# Circuit_Complet_Sinus.net
KiCad netlist of a schematic drawn in Altium Designer
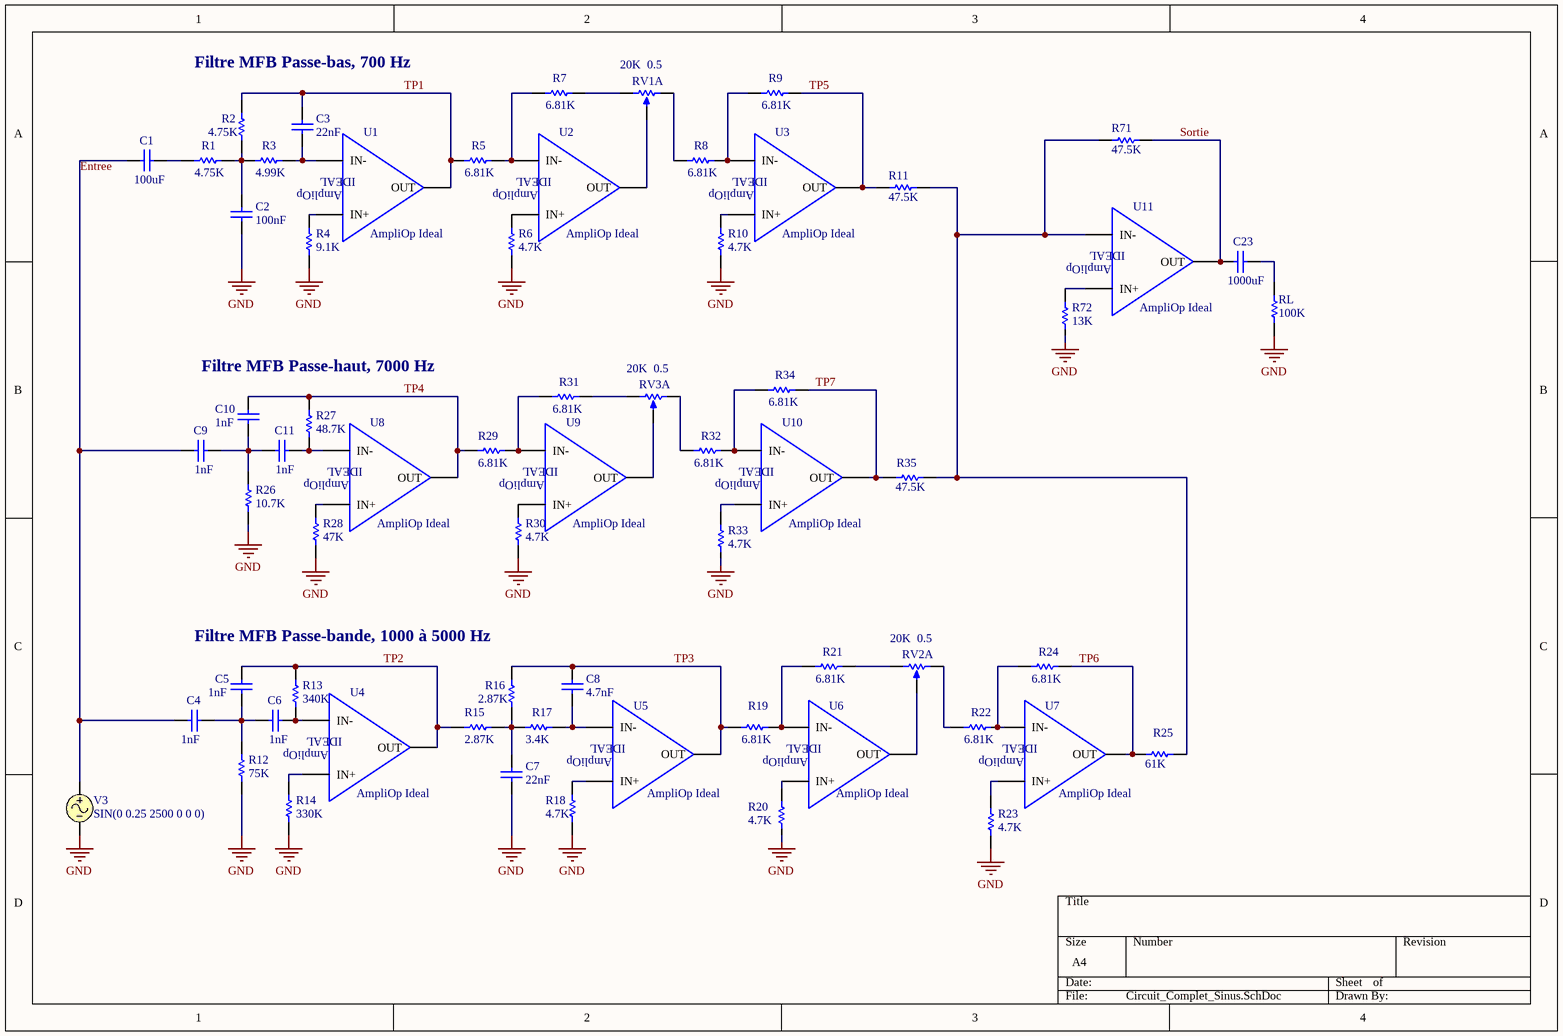
[diagram p0: Circuit_Complet_Sinus.SchDoc]

(export (version "E")
  (design (tool "Eeschema 10.0.6"))
  (components
    (comp (ref "C1")
      (value "100uF")
      (footprint "RAD-0.3")
      (description "Capacitor")
      (fields (field (name "Comment") "Cap") (field (name "PUBLISHER") "Altium Limited"))
      (libsource (lib "Miscellaneous Devices") (part "Cap"))
    )
    (comp (ref "C2")
      (value "100nF")
      (footprint "RAD-0.3")
      (description "Capacitor")
      (fields (field (name "Comment") "Cap") (field (name "PUBLISHER") "Altium Limited"))
      (libsource (lib "Miscellaneous Devices") (part "Cap"))
    )
    (comp (ref "C3")
      (value "22nF")
      (footprint "RAD-0.3")
      (description "Capacitor")
      (fields (field (name "Comment") "Cap") (field (name "PUBLISHER") "Altium Limited"))
      (libsource (lib "Miscellaneous Devices") (part "Cap"))
    )
    (comp (ref "C4")
      (value "1nF")
      (footprint "RAD-0.3")
      (description "Capacitor")
      (fields (field (name "Comment") "Cap") (field (name "PUBLISHER") "Altium Limited"))
      (libsource (lib "Miscellaneous Devices") (part "Cap"))
    )
    (comp (ref "C5")
      (value "1nF")
      (footprint "RAD-0.3")
      (description "Capacitor")
      (fields (field (name "Comment") "Cap") (field (name "PUBLISHER") "Altium Limited"))
      (libsource (lib "Miscellaneous Devices") (part "Cap"))
    )
    (comp (ref "C6")
      (value "1nF")
      (footprint "RAD-0.3")
      (description "Capacitor")
      (fields (field (name "Comment") "Cap") (field (name "PUBLISHER") "Altium Limited"))
      (libsource (lib "Miscellaneous Devices") (part "Cap"))
    )
    (comp (ref "C7")
      (value "22nF")
      (footprint "RAD-0.3")
      (description "Capacitor")
      (fields (field (name "Comment") "Cap") (field (name "PUBLISHER") "Altium Limited"))
      (libsource (lib "Miscellaneous Devices") (part "Cap"))
    )
    (comp (ref "C8")
      (value "4.7nF")
      (footprint "RAD-0.3")
      (description "Capacitor")
      (fields (field (name "Comment") "Cap") (field (name "PUBLISHER") "Altium Limited"))
      (libsource (lib "Miscellaneous Devices") (part "Cap"))
    )
    (comp (ref "C9")
      (value "1nF")
      (footprint "RAD-0.3")
      (description "Capacitor")
      (fields (field (name "Comment") "Cap") (field (name "PUBLISHER") "Altium Limited"))
      (libsource (lib "Miscellaneous Devices") (part "Cap"))
    )
    (comp (ref "C10")
      (value "1nF")
      (footprint "RAD-0.3")
      (description "Capacitor")
      (fields (field (name "Comment") "Cap") (field (name "PUBLISHER") "Altium Limited"))
      (libsource (lib "Miscellaneous Devices") (part "Cap"))
    )
    (comp (ref "C11")
      (value "1nF")
      (footprint "RAD-0.3")
      (description "Capacitor")
      (fields (field (name "Comment") "Cap") (field (name "PUBLISHER") "Altium Limited"))
      (libsource (lib "Miscellaneous Devices") (part "Cap"))
    )
    (comp (ref "C23")
      (value "1000uF")
      (footprint "RAD-0.3")
      (description "Capacitor")
      (fields (field (name "Comment") "Cap") (field (name "PUBLISHER") "Altium Limited"))
      (libsource (lib "Miscellaneous Devices") (part "Cap"))
    )
    (comp (ref "R1")
      (value "4.75K")
      (footprint "AXIAL-0.3")
      (description "Resistor")
      (fields (field (name "Comment") "Res1") (field (name "PUBLISHER") "Altium Limited"))
      (libsource (lib "Miscellaneous Devices") (part "Res1"))
    )
    (comp (ref "R2")
      (value "4.75K")
      (footprint "AXIAL-0.3")
      (description "Resistor")
      (fields (field (name "Comment") "Res1") (field (name "PUBLISHER") "Altium Limited"))
      (libsource (lib "Miscellaneous Devices") (part "Res1"))
    )
    (comp (ref "R3")
      (value "4.99K")
      (footprint "AXIAL-0.3")
      (description "Resistor")
      (fields (field (name "Comment") "Res1") (field (name "PUBLISHER") "Altium Limited"))
      (libsource (lib "Miscellaneous Devices") (part "Res1"))
    )
    (comp (ref "R4")
      (value "9.1K")
      (footprint "AXIAL-0.3")
      (description "Resistor")
      (fields (field (name "Comment") "Res1") (field (name "PUBLISHER") "Altium Limited"))
      (libsource (lib "Miscellaneous Devices") (part "Res1"))
    )
    (comp (ref "R5")
      (value "6.81K")
      (footprint "AXIAL-0.3")
      (description "Resistor")
      (fields (field (name "Comment") "Res1") (field (name "PUBLISHER") "Altium Limited"))
      (libsource (lib "Miscellaneous Devices") (part "Res1"))
    )
    (comp (ref "R6")
      (value "4.7K")
      (footprint "AXIAL-0.3")
      (description "Resistor")
      (fields (field (name "Comment") "Res1") (field (name "PUBLISHER") "Altium Limited"))
      (libsource (lib "Miscellaneous Devices") (part "Res1"))
    )
    (comp (ref "R7")
      (value "6.81K")
      (footprint "AXIAL-0.3")
      (description "Resistor")
      (fields (field (name "Comment") "Res1") (field (name "PUBLISHER") "Altium Limited"))
      (libsource (lib "Miscellaneous Devices") (part "Res1"))
    )
    (comp (ref "R8")
      (value "6.81K")
      (footprint "AXIAL-0.3")
      (description "Resistor")
      (fields (field (name "Comment") "Res1") (field (name "PUBLISHER") "Altium Limited"))
      (libsource (lib "Miscellaneous Devices") (part "Res1"))
    )
    (comp (ref "R9")
      (value "6.81K")
      (footprint "AXIAL-0.3")
      (description "Resistor")
      (fields (field (name "Comment") "Res1") (field (name "PUBLISHER") "Altium Limited"))
      (libsource (lib "Miscellaneous Devices") (part "Res1"))
    )
    (comp (ref "R10")
      (value "4.7K")
      (footprint "AXIAL-0.3")
      (description "Resistor")
      (fields (field (name "Comment") "Res1") (field (name "PUBLISHER") "Altium Limited"))
      (libsource (lib "Miscellaneous Devices") (part "Res1"))
    )
    (comp (ref "R11")
      (value "47.5K")
      (footprint "AXIAL-0.3")
      (description "Resistor")
      (fields (field (name "Comment") "Res1") (field (name "PUBLISHER") "Altium Limited"))
      (libsource (lib "Miscellaneous Devices") (part "Res1"))
    )
    (comp (ref "R12")
      (value "75K")
      (footprint "AXIAL-0.3")
      (description "Resistor")
      (fields (field (name "Comment") "Res1") (field (name "PUBLISHER") "Altium Limited"))
      (libsource (lib "Miscellaneous Devices") (part "Res1"))
    )
    (comp (ref "R13")
      (value "340K")
      (footprint "AXIAL-0.3")
      (description "Resistor")
      (fields (field (name "Comment") "Res1") (field (name "PUBLISHER") "Altium Limited"))
      (libsource (lib "Miscellaneous Devices") (part "Res1"))
    )
    (comp (ref "R14")
      (value "330K")
      (footprint "AXIAL-0.3")
      (description "Resistor")
      (fields (field (name "Comment") "Res1") (field (name "PUBLISHER") "Altium Limited"))
      (libsource (lib "Miscellaneous Devices") (part "Res1"))
    )
    (comp (ref "R15")
      (value "2.87K")
      (footprint "AXIAL-0.3")
      (description "Resistor")
      (fields (field (name "Comment") "Res1") (field (name "PUBLISHER") "Altium Limited"))
      (libsource (lib "Miscellaneous Devices") (part "Res1"))
    )
    (comp (ref "R16")
      (value "2.87K")
      (footprint "AXIAL-0.3")
      (description "Resistor")
      (fields (field (name "Comment") "Res1") (field (name "PUBLISHER") "Altium Limited"))
      (libsource (lib "Miscellaneous Devices") (part "Res1"))
    )
    (comp (ref "R17")
      (value "3.4K")
      (footprint "AXIAL-0.3")
      (description "Resistor")
      (fields (field (name "Comment") "Res1") (field (name "PUBLISHER") "Altium Limited"))
      (libsource (lib "Miscellaneous Devices") (part "Res1"))
    )
    (comp (ref "R18")
      (value "4.7K")
      (footprint "AXIAL-0.3")
      (description "Resistor")
      (fields (field (name "Comment") "Res1") (field (name "PUBLISHER") "Altium Limited"))
      (libsource (lib "Miscellaneous Devices") (part "Res1"))
    )
    (comp (ref "R19")
      (value "6.81K")
      (footprint "AXIAL-0.3")
      (description "Resistor")
      (fields (field (name "Comment") "Res1") (field (name "PUBLISHER") "Altium Limited"))
      (libsource (lib "Miscellaneous Devices") (part "Res1"))
    )
    (comp (ref "R20")
      (value "4.7K")
      (footprint "AXIAL-0.3")
      (description "Resistor")
      (fields (field (name "Comment") "Res1") (field (name "PUBLISHER") "Altium Limited"))
      (libsource (lib "Miscellaneous Devices") (part "Res1"))
    )
    (comp (ref "R21")
      (value "6.81K")
      (footprint "AXIAL-0.3")
      (description "Resistor")
      (fields (field (name "Comment") "Res1") (field (name "PUBLISHER") "Altium Limited"))
      (libsource (lib "Miscellaneous Devices") (part "Res1"))
    )
    (comp (ref "R22")
      (value "6.81K")
      (footprint "AXIAL-0.3")
      (description "Resistor")
      (fields (field (name "Comment") "Res1") (field (name "PUBLISHER") "Altium Limited"))
      (libsource (lib "Miscellaneous Devices") (part "Res1"))
    )
    (comp (ref "R23")
      (value "4.7K")
      (footprint "AXIAL-0.3")
      (description "Resistor")
      (fields (field (name "Comment") "Res1") (field (name "PUBLISHER") "Altium Limited"))
      (libsource (lib "Miscellaneous Devices") (part "Res1"))
    )
    (comp (ref "R24")
      (value "6.81K")
      (footprint "AXIAL-0.3")
      (description "Resistor")
      (fields (field (name "Comment") "Res1") (field (name "PUBLISHER") "Altium Limited"))
      (libsource (lib "Miscellaneous Devices") (part "Res1"))
    )
    (comp (ref "R25")
      (value "61K")
      (footprint "AXIAL-0.3")
      (description "Resistor")
      (fields (field (name "Comment") "Res1") (field (name "PUBLISHER") "Altium Limited"))
      (libsource (lib "Miscellaneous Devices") (part "Res1"))
    )
    (comp (ref "R26")
      (value "10.7K")
      (footprint "AXIAL-0.3")
      (description "Resistor")
      (fields (field (name "Comment") "Res1") (field (name "PUBLISHER") "Altium Limited"))
      (libsource (lib "Miscellaneous Devices") (part "Res1"))
    )
    (comp (ref "R27")
      (value "48.7K")
      (footprint "AXIAL-0.3")
      (description "Resistor")
      (fields (field (name "Comment") "Res1") (field (name "PUBLISHER") "Altium Limited"))
      (libsource (lib "Miscellaneous Devices") (part "Res1"))
    )
    (comp (ref "R28")
      (value "47K")
      (footprint "AXIAL-0.3")
      (description "Resistor")
      (fields (field (name "Comment") "Res1") (field (name "PUBLISHER") "Altium Limited"))
      (libsource (lib "Miscellaneous Devices") (part "Res1"))
    )
    (comp (ref "R29")
      (value "6.81K")
      (footprint "AXIAL-0.3")
      (description "Resistor")
      (fields (field (name "Comment") "Res1") (field (name "PUBLISHER") "Altium Limited"))
      (libsource (lib "Miscellaneous Devices") (part "Res1"))
    )
    (comp (ref "R30")
      (value "4.7K")
      (footprint "AXIAL-0.3")
      (description "Resistor")
      (fields (field (name "Comment") "Res1") (field (name "PUBLISHER") "Altium Limited"))
      (libsource (lib "Miscellaneous Devices") (part "Res1"))
    )
    (comp (ref "R31")
      (value "6.81K")
      (footprint "AXIAL-0.3")
      (description "Resistor")
      (fields (field (name "Comment") "Res1") (field (name "PUBLISHER") "Altium Limited"))
      (libsource (lib "Miscellaneous Devices") (part "Res1"))
    )
    (comp (ref "R32")
      (value "6.81K")
      (footprint "AXIAL-0.3")
      (description "Resistor")
      (fields (field (name "Comment") "Res1") (field (name "PUBLISHER") "Altium Limited"))
      (libsource (lib "Miscellaneous Devices") (part "Res1"))
    )
    (comp (ref "R33")
      (value "4.7K")
      (footprint "AXIAL-0.3")
      (description "Resistor")
      (fields (field (name "Comment") "Res1") (field (name "PUBLISHER") "Altium Limited"))
      (libsource (lib "Miscellaneous Devices") (part "Res1"))
    )
    (comp (ref "R34")
      (value "6.81K")
      (footprint "AXIAL-0.3")
      (description "Resistor")
      (fields (field (name "Comment") "Res1") (field (name "PUBLISHER") "Altium Limited"))
      (libsource (lib "Miscellaneous Devices") (part "Res1"))
    )
    (comp (ref "R35")
      (value "47.5K")
      (footprint "AXIAL-0.3")
      (description "Resistor")
      (fields (field (name "Comment") "Res1") (field (name "PUBLISHER") "Altium Limited"))
      (libsource (lib "Miscellaneous Devices") (part "Res1"))
    )
    (comp (ref "R71")
      (value "47.5K")
      (footprint "AXIAL-0.3")
      (description "Resistor")
      (fields (field (name "Comment") "Res1") (field (name "PUBLISHER") "Altium Limited"))
      (libsource (lib "Miscellaneous Devices") (part "Res1"))
    )
    (comp (ref "R72")
      (value "13K")
      (footprint "AXIAL-0.3")
      (description "Resistor")
      (fields (field (name "Comment") "Res1") (field (name "PUBLISHER") "Altium Limited"))
      (libsource (lib "Miscellaneous Devices") (part "Res1"))
    )
    (comp (ref "RL")
      (value "100K")
      (footprint "AXIAL-0.3")
      (description "Resistor")
      (fields (field (name "Comment") "Res1") (field (name "PUBLISHER") "Altium Limited"))
      (libsource (lib "Miscellaneous Devices") (part "Res1"))
    )
    (comp (ref "RV1A")
      (value "20K")
      (footprint "VR5")
      (description "Potentiometer")
      (fields
        (field (name "SET POSITION") "0.5")
        (field (name "Comment") "RPot")
        (field (name "PUBLISHER") "Altium Limited")
      )
      (libsource (lib "Miscellaneous Devices") (part "RPot"))
    )
    (comp (ref "RV2A")
      (value "20K")
      (footprint "VR5")
      (description "Potentiometer")
      (fields
        (field (name "SET POSITION") "0.5")
        (field (name "Comment") "RPot")
        (field (name "PUBLISHER") "Altium Limited")
      )
      (libsource (lib "Miscellaneous Devices") (part "RPot"))
    )
    (comp (ref "RV3A")
      (value "20K")
      (footprint "VR5")
      (description "Potentiometer")
      (fields
        (field (name "SET POSITION") "0.5")
        (field (name "Comment") "RPot")
        (field (name "PUBLISHER") "Altium Limited")
      )
      (libsource (lib "Miscellaneous Devices") (part "RPot"))
    )
    (comp (ref "U1") (value "AmpliOp Ideal") (libsource (lib "Librarie_S2") (part "AmpliOp_ideal")))
    (comp (ref "U2") (value "AmpliOp Ideal") (libsource (lib "Librarie_S2") (part "AmpliOp_ideal")))
    (comp (ref "U3") (value "AmpliOp Ideal") (libsource (lib "Librarie_S2") (part "AmpliOp_ideal")))
    (comp (ref "U4") (value "AmpliOp Ideal") (libsource (lib "Librarie_S2") (part "AmpliOp_ideal")))
    (comp (ref "U5") (value "AmpliOp Ideal") (libsource (lib "Librarie_S2") (part "AmpliOp_ideal")))
    (comp (ref "U6") (value "AmpliOp Ideal") (libsource (lib "Librarie_S2") (part "AmpliOp_ideal")))
    (comp (ref "U7") (value "AmpliOp Ideal") (libsource (lib "Librarie_S2") (part "AmpliOp_ideal")))
    (comp (ref "U8") (value "AmpliOp Ideal") (libsource (lib "Librarie_S2") (part "AmpliOp_ideal")))
    (comp (ref "U9") (value "AmpliOp Ideal") (libsource (lib "Librarie_S2") (part "AmpliOp_ideal")))
    (comp (ref "U10") (value "AmpliOp Ideal") (libsource (lib "Librarie_S2") (part "AmpliOp_ideal")))
    (comp (ref "U11") (value "AmpliOp Ideal") (libsource (lib "Librarie_S2") (part "AmpliOp_ideal")))
    (comp (ref "V3")
      (value "SIN(0 0.25 2500 0 0 0)")
      (description "Sinusoidal Voltage Source")
      (fields (field (name "PUBLISHER") "Altium Limited"))
      (libsource (lib "Simulation Sources") (part "VSIN"))
    )
  )
  (nets
    (net (code "1") (name "/Entree") (class "Default")
      (node (ref "C1") (pin "1") (pinfunction "1_1") (pintype "passive"))
      (node (ref "C4") (pin "1") (pinfunction "1_1") (pintype "passive"))
      (node (ref "C9") (pin "1") (pinfunction "1_1") (pintype "passive"))
      (node (ref "V3") (pin "1") (pinfunction "1_1") (pintype "passive"))
    )
    (net (code "2") (name "/Sortie") (class "Default")
      (node (ref "C23") (pin "1") (pinfunction "1_1") (pintype "passive"))
      (node (ref "R71") (pin "2") (pinfunction "2_2") (pintype "passive"))
      (node (ref "U11") (pin "3") (pinfunction "OUT_3") (pintype "passive"))
    )
    (net (code "3") (name "/TP1") (class "Default")
      (node (ref "C3") (pin "1") (pinfunction "1_1") (pintype "passive"))
      (node (ref "R2") (pin "1") (pinfunction "1_1") (pintype "passive"))
      (node (ref "R5") (pin "1") (pinfunction "1_1") (pintype "passive"))
      (node (ref "U1") (pin "3") (pinfunction "OUT_3") (pintype "passive"))
    )
    (net (code "4") (name "/TP2") (class "Default")
      (node (ref "C5") (pin "1") (pinfunction "1_1") (pintype "passive"))
      (node (ref "R13") (pin "1") (pinfunction "1_1") (pintype "passive"))
      (node (ref "R15") (pin "1") (pinfunction "1_1") (pintype "passive"))
      (node (ref "U4") (pin "3") (pinfunction "OUT_3") (pintype "passive"))
    )
    (net (code "5") (name "/TP3") (class "Default")
      (node (ref "C8") (pin "1") (pinfunction "1_1") (pintype "passive"))
      (node (ref "R16") (pin "1") (pinfunction "1_1") (pintype "passive"))
      (node (ref "R19") (pin "1") (pinfunction "1_1") (pintype "passive"))
      (node (ref "U5") (pin "3") (pinfunction "OUT_3") (pintype "passive"))
    )
    (net (code "6") (name "/TP4") (class "Default")
      (node (ref "C10") (pin "1") (pinfunction "1_1") (pintype "passive"))
      (node (ref "R27") (pin "1") (pinfunction "1_1") (pintype "passive"))
      (node (ref "R29") (pin "1") (pinfunction "1_1") (pintype "passive"))
      (node (ref "U8") (pin "3") (pinfunction "OUT_3") (pintype "passive"))
    )
    (net (code "7") (name "/TP5") (class "Default")
      (node (ref "R11") (pin "1") (pinfunction "1_1") (pintype "passive"))
      (node (ref "R9") (pin "2") (pinfunction "2_2") (pintype "passive"))
      (node (ref "U3") (pin "3") (pinfunction "OUT_3") (pintype "passive"))
    )
    (net (code "8") (name "/TP6") (class "Default")
      (node (ref "R24") (pin "2") (pinfunction "2_2") (pintype "passive"))
      (node (ref "R25") (pin "1") (pinfunction "1_1") (pintype "passive"))
      (node (ref "U7") (pin "3") (pinfunction "OUT_3") (pintype "passive"))
    )
    (net (code "9") (name "/TP7") (class "Default")
      (node (ref "R34") (pin "2") (pinfunction "2_2") (pintype "passive"))
      (node (ref "R35") (pin "1") (pinfunction "1_1") (pintype "passive"))
      (node (ref "U10") (pin "3") (pinfunction "OUT_3") (pintype "passive"))
    )
    (net (code "10") (name "GND") (class "Default")
      (node (ref "C2") (pin "2") (pinfunction "2_2") (pintype "passive"))
      (node (ref "C7") (pin "2") (pinfunction "2_2") (pintype "passive"))
      (node (ref "R10") (pin "2") (pinfunction "2_2") (pintype "passive"))
      (node (ref "R12") (pin "2") (pinfunction "2_2") (pintype "passive"))
      (node (ref "R14") (pin "2") (pinfunction "2_2") (pintype "passive"))
      (node (ref "R18") (pin "2") (pinfunction "2_2") (pintype "passive"))
      (node (ref "R20") (pin "2") (pinfunction "2_2") (pintype "passive"))
      (node (ref "R23") (pin "2") (pinfunction "2_2") (pintype "passive"))
      (node (ref "R26") (pin "2") (pinfunction "2_2") (pintype "passive"))
      (node (ref "R28") (pin "2") (pinfunction "2_2") (pintype "passive"))
      (node (ref "R30") (pin "2") (pinfunction "2_2") (pintype "passive"))
      (node (ref "R33") (pin "2") (pinfunction "2_2") (pintype "passive"))
      (node (ref "R4") (pin "2") (pinfunction "2_2") (pintype "passive"))
      (node (ref "R6") (pin "2") (pinfunction "2_2") (pintype "passive"))
      (node (ref "R72") (pin "2") (pinfunction "2_2") (pintype "passive"))
      (node (ref "RL") (pin "1") (pinfunction "1_1") (pintype "passive"))
      (node (ref "V3") (pin "2") (pinfunction "2_2") (pintype "passive"))
    )
    (net (code "11") (name "Net-(C1-Pad2)") (class "Default")
      (node (ref "C1") (pin "2") (pinfunction "2_2") (pintype "passive"))
      (node (ref "R1") (pin "1") (pinfunction "1_1") (pintype "passive"))
    )
    (net (code "12") (name "Net-(C2-Pad1)") (class "Default")
      (node (ref "C2") (pin "1") (pinfunction "1_1") (pintype "passive"))
      (node (ref "R1") (pin "2") (pinfunction "2_2") (pintype "passive"))
      (node (ref "R2") (pin "2") (pinfunction "2_2") (pintype "passive"))
      (node (ref "R3") (pin "1") (pinfunction "1_1") (pintype "passive"))
    )
    (net (code "13") (name "Net-(C4-Pad2)") (class "Default")
      (node (ref "C4") (pin "2") (pinfunction "2_2") (pintype "passive"))
      (node (ref "C5") (pin "2") (pinfunction "2_2") (pintype "passive"))
      (node (ref "C6") (pin "1") (pinfunction "1_1") (pintype "passive"))
      (node (ref "R12") (pin "1") (pinfunction "1_1") (pintype "passive"))
    )
    (net (code "14") (name "Net-(C7-Pad1)") (class "Default")
      (node (ref "C7") (pin "1") (pinfunction "1_1") (pintype "passive"))
      (node (ref "R15") (pin "2") (pinfunction "2_2") (pintype "passive"))
      (node (ref "R16") (pin "2") (pinfunction "2_2") (pintype "passive"))
      (node (ref "R17") (pin "1") (pinfunction "1_1") (pintype "passive"))
    )
    (net (code "15") (name "Net-(C10-Pad2)") (class "Default")
      (node (ref "C10") (pin "2") (pinfunction "2_2") (pintype "passive"))
      (node (ref "C11") (pin "1") (pinfunction "1_1") (pintype "passive"))
      (node (ref "C9") (pin "2") (pinfunction "2_2") (pintype "passive"))
      (node (ref "R26") (pin "1") (pinfunction "1_1") (pintype "passive"))
    )
    (net (code "16") (name "Net-(C23-Pad2)") (class "Default")
      (node (ref "C23") (pin "2") (pinfunction "2_2") (pintype "passive"))
      (node (ref "RL") (pin "2") (pinfunction "2_2") (pintype "passive"))
    )
    (net (code "17") (name "Net-(RV1A-BOT)") (class "Default")
      (node (ref "R8") (pin "1") (pinfunction "1_1") (pintype "passive"))
      (node (ref "RV1A") (pin "2") (pinfunction "BOT_2") (pintype "passive"))
    )
    (net (code "18") (name "Net-(RV1A-TAP)") (class "Default")
      (node (ref "RV1A") (pin "3") (pinfunction "TAP_3") (pintype "passive"))
      (node (ref "U2") (pin "3") (pinfunction "OUT_3") (pintype "passive"))
    )
    (net (code "19") (name "Net-(RV1A-TOP)") (class "Default")
      (node (ref "R7") (pin "2") (pinfunction "2_2") (pintype "passive"))
      (node (ref "RV1A") (pin "1") (pinfunction "TOP_1") (pintype "passive"))
    )
    (net (code "20") (name "Net-(RV2A-BOT)") (class "Default")
      (node (ref "R22") (pin "1") (pinfunction "1_1") (pintype "passive"))
      (node (ref "RV2A") (pin "2") (pinfunction "BOT_2") (pintype "passive"))
    )
    (net (code "21") (name "Net-(RV2A-TAP)") (class "Default")
      (node (ref "RV2A") (pin "3") (pinfunction "TAP_3") (pintype "passive"))
      (node (ref "U6") (pin "3") (pinfunction "OUT_3") (pintype "passive"))
    )
    (net (code "22") (name "Net-(RV2A-TOP)") (class "Default")
      (node (ref "R21") (pin "2") (pinfunction "2_2") (pintype "passive"))
      (node (ref "RV2A") (pin "1") (pinfunction "TOP_1") (pintype "passive"))
    )
    (net (code "23") (name "Net-(RV3A-BOT)") (class "Default")
      (node (ref "R32") (pin "1") (pinfunction "1_1") (pintype "passive"))
      (node (ref "RV3A") (pin "2") (pinfunction "BOT_2") (pintype "passive"))
    )
    (net (code "24") (name "Net-(RV3A-TAP)") (class "Default")
      (node (ref "RV3A") (pin "3") (pinfunction "TAP_3") (pintype "passive"))
      (node (ref "U9") (pin "3") (pinfunction "OUT_3") (pintype "passive"))
    )
    (net (code "25") (name "Net-(RV3A-TOP)") (class "Default")
      (node (ref "R31") (pin "2") (pinfunction "2_2") (pintype "passive"))
      (node (ref "RV3A") (pin "1") (pinfunction "TOP_1") (pintype "passive"))
    )
    (net (code "26") (name "Net-(U1-IN+)") (class "Default")
      (node (ref "R4") (pin "1") (pinfunction "1_1") (pintype "passive"))
      (node (ref "U1") (pin "1") (pinfunction "IN+_1") (pintype "passive"))
    )
    (net (code "27") (name "Net-(U1-IN-)") (class "Default")
      (node (ref "C3") (pin "2") (pinfunction "2_2") (pintype "passive"))
      (node (ref "R3") (pin "2") (pinfunction "2_2") (pintype "passive"))
      (node (ref "U1") (pin "2") (pinfunction "IN-_2") (pintype "passive"))
    )
    (net (code "28") (name "Net-(U2-IN+)") (class "Default")
      (node (ref "R6") (pin "1") (pinfunction "1_1") (pintype "passive"))
      (node (ref "U2") (pin "1") (pinfunction "IN+_1") (pintype "passive"))
    )
    (net (code "29") (name "Net-(U2-IN-)") (class "Default")
      (node (ref "R5") (pin "2") (pinfunction "2_2") (pintype "passive"))
      (node (ref "R7") (pin "1") (pinfunction "1_1") (pintype "passive"))
      (node (ref "U2") (pin "2") (pinfunction "IN-_2") (pintype "passive"))
    )
    (net (code "30") (name "Net-(U3-IN+)") (class "Default")
      (node (ref "R10") (pin "1") (pinfunction "1_1") (pintype "passive"))
      (node (ref "U3") (pin "1") (pinfunction "IN+_1") (pintype "passive"))
    )
    (net (code "31") (name "Net-(U3-IN-)") (class "Default")
      (node (ref "R8") (pin "2") (pinfunction "2_2") (pintype "passive"))
      (node (ref "R9") (pin "1") (pinfunction "1_1") (pintype "passive"))
      (node (ref "U3") (pin "2") (pinfunction "IN-_2") (pintype "passive"))
    )
    (net (code "32") (name "Net-(U4-IN+)") (class "Default")
      (node (ref "R14") (pin "1") (pinfunction "1_1") (pintype "passive"))
      (node (ref "U4") (pin "1") (pinfunction "IN+_1") (pintype "passive"))
    )
    (net (code "33") (name "Net-(U4-IN-)") (class "Default")
      (node (ref "C6") (pin "2") (pinfunction "2_2") (pintype "passive"))
      (node (ref "R13") (pin "2") (pinfunction "2_2") (pintype "passive"))
      (node (ref "U4") (pin "2") (pinfunction "IN-_2") (pintype "passive"))
    )
    (net (code "34") (name "Net-(U5-IN+)") (class "Default")
      (node (ref "R18") (pin "1") (pinfunction "1_1") (pintype "passive"))
      (node (ref "U5") (pin "1") (pinfunction "IN+_1") (pintype "passive"))
    )
    (net (code "35") (name "Net-(U5-IN-)") (class "Default")
      (node (ref "C8") (pin "2") (pinfunction "2_2") (pintype "passive"))
      (node (ref "R17") (pin "2") (pinfunction "2_2") (pintype "passive"))
      (node (ref "U5") (pin "2") (pinfunction "IN-_2") (pintype "passive"))
    )
    (net (code "36") (name "Net-(U6-IN+)") (class "Default")
      (node (ref "R20") (pin "1") (pinfunction "1_1") (pintype "passive"))
      (node (ref "U6") (pin "1") (pinfunction "IN+_1") (pintype "passive"))
    )
    (net (code "37") (name "Net-(U6-IN-)") (class "Default")
      (node (ref "R19") (pin "2") (pinfunction "2_2") (pintype "passive"))
      (node (ref "R21") (pin "1") (pinfunction "1_1") (pintype "passive"))
      (node (ref "U6") (pin "2") (pinfunction "IN-_2") (pintype "passive"))
    )
    (net (code "38") (name "Net-(U7-IN+)") (class "Default")
      (node (ref "R23") (pin "1") (pinfunction "1_1") (pintype "passive"))
      (node (ref "U7") (pin "1") (pinfunction "IN+_1") (pintype "passive"))
    )
    (net (code "39") (name "Net-(U7-IN-)") (class "Default")
      (node (ref "R22") (pin "2") (pinfunction "2_2") (pintype "passive"))
      (node (ref "R24") (pin "1") (pinfunction "1_1") (pintype "passive"))
      (node (ref "U7") (pin "2") (pinfunction "IN-_2") (pintype "passive"))
    )
    (net (code "40") (name "Net-(U8-IN+)") (class "Default")
      (node (ref "R28") (pin "1") (pinfunction "1_1") (pintype "passive"))
      (node (ref "U8") (pin "1") (pinfunction "IN+_1") (pintype "passive"))
    )
    (net (code "41") (name "Net-(U8-IN-)") (class "Default")
      (node (ref "C11") (pin "2") (pinfunction "2_2") (pintype "passive"))
      (node (ref "R27") (pin "2") (pinfunction "2_2") (pintype "passive"))
      (node (ref "U8") (pin "2") (pinfunction "IN-_2") (pintype "passive"))
    )
    (net (code "42") (name "Net-(U9-IN+)") (class "Default")
      (node (ref "R30") (pin "1") (pinfunction "1_1") (pintype "passive"))
      (node (ref "U9") (pin "1") (pinfunction "IN+_1") (pintype "passive"))
    )
    (net (code "43") (name "Net-(U9-IN-)") (class "Default")
      (node (ref "R29") (pin "2") (pinfunction "2_2") (pintype "passive"))
      (node (ref "R31") (pin "1") (pinfunction "1_1") (pintype "passive"))
      (node (ref "U9") (pin "2") (pinfunction "IN-_2") (pintype "passive"))
    )
    (net (code "44") (name "Net-(U10-IN+)") (class "Default")
      (node (ref "R33") (pin "1") (pinfunction "1_1") (pintype "passive"))
      (node (ref "U10") (pin "1") (pinfunction "IN+_1") (pintype "passive"))
    )
    (net (code "45") (name "Net-(U10-IN-)") (class "Default")
      (node (ref "R32") (pin "2") (pinfunction "2_2") (pintype "passive"))
      (node (ref "R34") (pin "1") (pinfunction "1_1") (pintype "passive"))
      (node (ref "U10") (pin "2") (pinfunction "IN-_2") (pintype "passive"))
    )
    (net (code "46") (name "Net-(U11-IN+)") (class "Default")
      (node (ref "R72") (pin "1") (pinfunction "1_1") (pintype "passive"))
      (node (ref "U11") (pin "1") (pinfunction "IN+_1") (pintype "passive"))
    )
    (net (code "47") (name "Net-(U11-IN-)") (class "Default")
      (node (ref "R11") (pin "2") (pinfunction "2_2") (pintype "passive"))
      (node (ref "R25") (pin "2") (pinfunction "2_2") (pintype "passive"))
      (node (ref "R35") (pin "2") (pinfunction "2_2") (pintype "passive"))
      (node (ref "R71") (pin "1") (pinfunction "1_1") (pintype "passive"))
      (node (ref "U11") (pin "2") (pinfunction "IN-_2") (pintype "passive"))
    )
  )
)
